# RainbowLED_2021_05_02_A.net
KiCad netlist of a schematic drawn in EAGLE
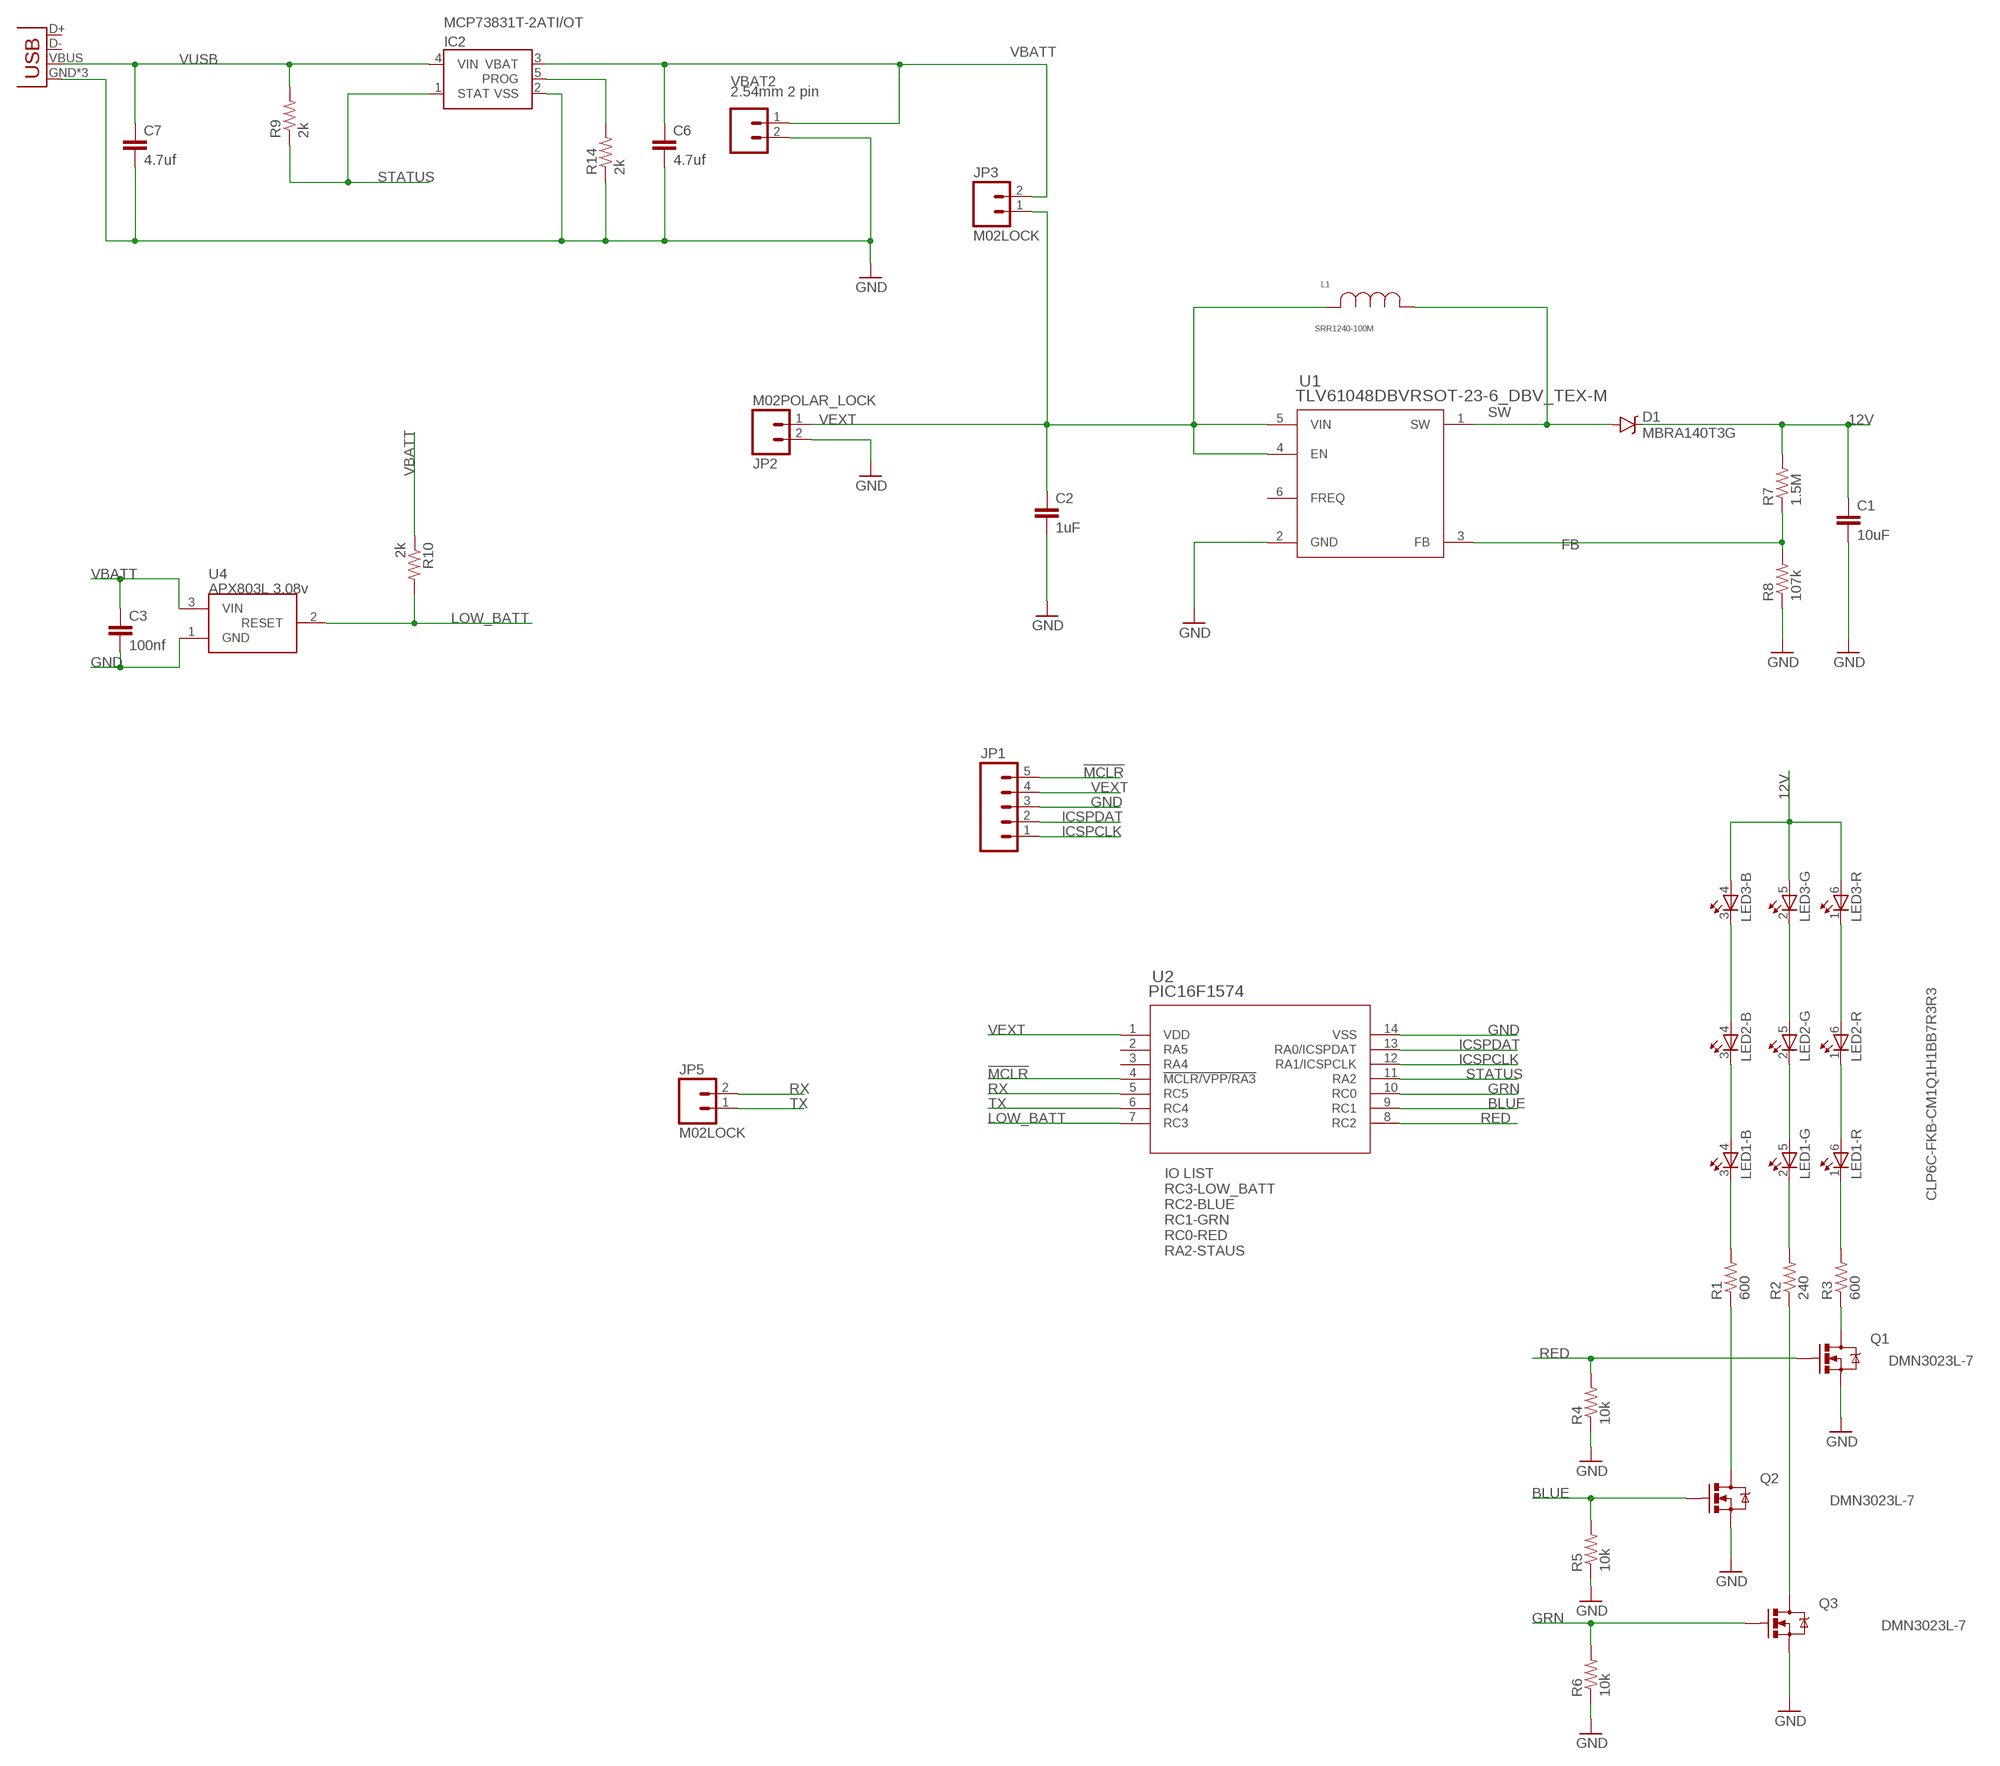
[diagram p0: schematic, sheet 1]

(export (version "E")
  (design (tool "Eeschema 10.0.6"))
  (components
    (comp (ref "C1")
      (value "10uF")
      (footprint "eagle-import:1206")
      (libsource (lib "eagle-import") (part "CAP1206"))
    )
    (comp (ref "C2")
      (value "1uF")
      (footprint "eagle-import:1206")
      (libsource (lib "eagle-import") (part "CAP1206"))
    )
    (comp (ref "C3")
      (value "100nf")
      (footprint "eagle-import:1206")
      (libsource (lib "eagle-import") (part "CAP1206"))
    )
    (comp (ref "C6")
      (value "4.7uf")
      (footprint "eagle-import:1206")
      (libsource (lib "eagle-import") (part "CAP1206"))
    )
    (comp (ref "C7")
      (value "4.7uf")
      (footprint "eagle-import:1206")
      (libsource (lib "eagle-import") (part "CAP1206"))
    )
    (comp (ref "D1")
      (value "MBRA140T3G")
      (footprint "eagle-import:SMA-DIODE")
      (libsource (lib "eagle-import") (part "DIODE-SCHOTTKY-MBRA140"))
    )
    (comp (ref "IC2")
      (value "MCP73831T-2ATI/OT")
      (footprint "eagle-import:SOT23-5")
      (libsource (lib "eagle-import") (part "MCP73831"))
    )
    (comp (ref "JP1")
      (value "M05LOCK")
      (footprint "eagle-import:1X05_LOCK")
      (libsource (lib "eagle-import") (part "M05LOCK"))
    )
    (comp (ref "JP2")
      (value "M02POLAR_LOCK")
      (footprint "eagle-import:MOLEX-1X2_LOCK")
      (libsource (lib "eagle-import") (part "M02POLAR_LOCK"))
    )
    (comp (ref "JP3")
      (value "M02LOCK")
      (footprint "eagle-import:1X02_LOCK")
      (libsource (lib "eagle-import") (part "M02LOCK"))
    )
    (comp (ref "JP4")
      (value "USB-MICROB")
      (footprint "eagle-import:USB-MICROB")
      (libsource (lib "eagle-import") (part "USB-MICROB"))
    )
    (comp (ref "JP5")
      (value "M02LOCK")
      (footprint "eagle-import:1X02_LOCK")
      (libsource (lib "eagle-import") (part "M02LOCK"))
    )
    (comp (ref "L1")
      (value "SRR1240-100M")
      (footprint "eagle-import:IND_BOURNS_SRR1240")
      (fields (field (name "MANUFACTURER_PART_NUMBER") "SRR1240100M"))
      (libsource (lib "eagle-import") (part "SRR1240-100M"))
    )
    (comp (ref "LED1")
      (value "CLX6F-FKC-CKNNQDGBB7A363")
      (footprint "eagle-import:PLCC-6")
      (libsource (lib "eagle-import") (part "OVSTRGBBCR8"))
    )
    (comp (ref "LED2")
      (value "CLX6F-FKC-CKNNQDGBB7A363")
      (footprint "eagle-import:PLCC-6")
      (libsource (lib "eagle-import") (part "OVSTRGBBCR8"))
    )
    (comp (ref "LED3")
      (value "CLX6F-FKC-CKNNQDGBB7A363")
      (footprint "eagle-import:PLCC-6")
      (libsource (lib "eagle-import") (part "OVSTRGBBCR8"))
    )
    (comp (ref "Q1")
      (value "DMN3023L-7")
      (footprint "eagle-import:SOT23-3")
      (libsource (lib "eagle-import") (part "MOSFET-NCHANNELBSS138"))
    )
    (comp (ref "Q2")
      (value "DMN3023L-7")
      (footprint "eagle-import:SOT23-3")
      (libsource (lib "eagle-import") (part "MOSFET-NCHANNELBSS138"))
    )
    (comp (ref "Q3")
      (value "DMN3023L-7")
      (footprint "eagle-import:SOT23-3")
      (libsource (lib "eagle-import") (part "MOSFET-NCHANNELBSS138"))
    )
    (comp (ref "R1")
      (value "600")
      (footprint "eagle-import:1206")
      (libsource (lib "eagle-import") (part "RESISTOR1206"))
    )
    (comp (ref "R2")
      (value "240")
      (footprint "eagle-import:1206")
      (libsource (lib "eagle-import") (part "RESISTOR1206"))
    )
    (comp (ref "R3")
      (value "600")
      (footprint "eagle-import:1206")
      (libsource (lib "eagle-import") (part "RESISTOR1206"))
    )
    (comp (ref "R4")
      (value "10k")
      (footprint "eagle-import:1206")
      (libsource (lib "eagle-import") (part "RESISTOR1206"))
    )
    (comp (ref "R5")
      (value "10k")
      (footprint "eagle-import:1206")
      (libsource (lib "eagle-import") (part "RESISTOR1206"))
    )
    (comp (ref "R6")
      (value "10k")
      (footprint "eagle-import:1206")
      (libsource (lib "eagle-import") (part "RESISTOR1206"))
    )
    (comp (ref "R7")
      (value "1.5M")
      (footprint "eagle-import:1206")
      (libsource (lib "eagle-import") (part "RESISTOR1206"))
    )
    (comp (ref "R8")
      (value "107k")
      (footprint "eagle-import:1206")
      (libsource (lib "eagle-import") (part "RESISTOR1206"))
    )
    (comp (ref "R9")
      (value "2k")
      (footprint "eagle-import:1206")
      (libsource (lib "eagle-import") (part "SparkFun-Resistors_RESISTOR1206"))
    )
    (comp (ref "R10")
      (value "2k")
      (footprint "eagle-import:1206")
      (libsource (lib "eagle-import") (part "SparkFun-Resistors_RESISTOR1206"))
    )
    (comp (ref "R14")
      (value "2k")
      (footprint "eagle-import:1206")
      (libsource (lib "eagle-import") (part "SparkFun-Resistors_RESISTOR1206"))
    )
    (comp (ref "U1")
      (value "TLV61048DBVRSOT-23-6_DBV_TEX-M")
      (footprint "eagle-import:SOT-23-6_DBV_TEX-M")
      (fields
        (field (name "MANUFACTURER_PART_NUMBER") "TLV61048DBVR")
        (field (name "COPYRIGHT") "Copyright (C) 2018 Accelerated Designs. All rights reserved")
      )
      (libsource (lib "eagle-import") (part "TLV61048DBVRSOT-23-6_DBV_TEX-M"))
    )
    (comp (ref "U2")
      (value "PIC16F1574")
      (footprint "eagle-import:SOIC14_SL")
      (fields (field (name "MANUFACTURER_PART_NUMBER") "PIC16F1503-I/SL"))
      (libsource (lib "eagle-import") (part "PIC16F1503-I/SL"))
    )
    (comp (ref "U4")
      (value "APX803L 3.08v")
      (footprint "eagle-import:SOT23")
      (libsource (lib "eagle-import") (part "ADP160"))
    )
    (comp (ref "VBAT2")
      (value "2.54mm 2 pin")
      (footprint "eagle-import:JST-2-PTH-VERT")
      (libsource (lib "eagle-import") (part "M02JST-PTH-VERT"))
    )
  )
  (nets
    (net (code "1") (name "/12V") (class "Default")
      (node (ref "C1") (pin "1") (pinfunction "1_1") (pintype "passive"))
      (node (ref "D1") (pin "C") (pinfunction "C_C") (pintype "passive"))
      (node (ref "LED3") (pin "4") (pinfunction "A_4") (pintype "passive"))
      (node (ref "LED3") (pin "5") (pinfunction "A_5") (pintype "passive"))
      (node (ref "LED3") (pin "6") (pinfunction "A_6") (pintype "passive"))
      (node (ref "R7") (pin "2") (pinfunction "2_2") (pintype "passive"))
    )
    (net (code "2") (name "/BLUE") (class "Default")
      (node (ref "Q2") (pin "1") (pinfunction "G_1") (pintype "passive"))
      (node (ref "R5") (pin "2") (pinfunction "2_2") (pintype "passive"))
      (node (ref "U2") (pin "9") (pinfunction "RC1_9") (pintype "bidirectional"))
    )
    (net (code "3") (name "/FB") (class "Default")
      (node (ref "R7") (pin "1") (pinfunction "1_1") (pintype "passive"))
      (node (ref "R8") (pin "2") (pinfunction "2_2") (pintype "passive"))
      (node (ref "U1") (pin "3") (pinfunction "FB_3") (pintype "input"))
    )
    (net (code "4") (name "/GRN") (class "Default")
      (node (ref "Q3") (pin "1") (pinfunction "G_1") (pintype "passive"))
      (node (ref "R6") (pin "2") (pinfunction "2_2") (pintype "passive"))
      (node (ref "U2") (pin "10") (pinfunction "RC0_10") (pintype "bidirectional"))
    )
    (net (code "5") (name "/ICSPCLK") (class "Default")
      (node (ref "JP1") (pin "1") (pinfunction "1_1") (pintype "passive"))
      (node (ref "U2") (pin "12") (pinfunction "RA1/ICSPCLK_12") (pintype "bidirectional"))
    )
    (net (code "6") (name "/ICSPDAT") (class "Default")
      (node (ref "JP1") (pin "2") (pinfunction "2_2") (pintype "passive"))
      (node (ref "U2") (pin "13") (pinfunction "RA0/ICSPDAT_13") (pintype "bidirectional"))
    )
    (net (code "7") (name "/LOW_BATT") (class "Default")
      (node (ref "R10") (pin "2") (pinfunction "2_2") (pintype "passive"))
      (node (ref "U2") (pin "7") (pinfunction "RC3_7") (pintype "bidirectional"))
      (node (ref "U4") (pin "2") (pinfunction "RESET_2") (pintype "bidirectional"))
    )
    (net (code "8") (name "/RED") (class "Default")
      (node (ref "Q1") (pin "1") (pinfunction "G_1") (pintype "passive"))
      (node (ref "R4") (pin "2") (pinfunction "2_2") (pintype "passive"))
      (node (ref "U2") (pin "8") (pinfunction "RC2_8") (pintype "bidirectional"))
    )
    (net (code "9") (name "/RX") (class "Default")
      (node (ref "JP5") (pin "2") (pinfunction "2_2") (pintype "passive"))
      (node (ref "U2") (pin "5") (pinfunction "RC5_5") (pintype "bidirectional"))
    )
    (net (code "10") (name "/STATUS") (class "Default")
      (node (ref "IC2") (pin "1") (pinfunction "STAT_1") (pintype "output"))
      (node (ref "R9") (pin "1") (pinfunction "1_1") (pintype "passive"))
      (node (ref "U2") (pin "11") (pinfunction "RA2_11") (pintype "bidirectional"))
    )
    (net (code "11") (name "/SW") (class "Default")
      (node (ref "D1") (pin "A") (pinfunction "A_A") (pintype "passive"))
      (node (ref "L1") (pin "1") (pinfunction "1_1") (pintype "passive"))
      (node (ref "U1") (pin "1") (pinfunction "SW_1") (pintype "power_in"))
    )
    (net (code "12") (name "/TX") (class "Default")
      (node (ref "JP5") (pin "1") (pinfunction "1_1") (pintype "passive"))
      (node (ref "U2") (pin "6") (pinfunction "RC4_6") (pintype "bidirectional"))
    )
    (net (code "13") (name "/VBATT") (class "Default")
      (node (ref "C3") (pin "1") (pinfunction "1_1") (pintype "passive"))
      (node (ref "C6") (pin "1") (pinfunction "1_1") (pintype "passive"))
      (node (ref "IC2") (pin "3") (pinfunction "VBAT_3") (pintype "power_in"))
      (node (ref "JP3") (pin "2") (pinfunction "2_2") (pintype "passive"))
      (node (ref "R10") (pin "1") (pinfunction "1_1") (pintype "passive"))
      (node (ref "U4") (pin "3") (pinfunction "VIN_3") (pintype "bidirectional"))
      (node (ref "VBAT2") (pin "1") (pinfunction "1_1") (pintype "passive"))
    )
    (net (code "14") (name "/VEXT") (class "Default")
      (node (ref "C2") (pin "1") (pinfunction "1_1") (pintype "passive"))
      (node (ref "JP1") (pin "4") (pinfunction "4_4") (pintype "passive"))
      (node (ref "JP2") (pin "1") (pinfunction "1_1") (pintype "passive"))
      (node (ref "JP3") (pin "1") (pinfunction "1_1") (pintype "passive"))
      (node (ref "L1") (pin "2") (pinfunction "2_2") (pintype "passive"))
      (node (ref "U1") (pin "4") (pinfunction "EN_4") (pintype "input"))
      (node (ref "U1") (pin "5") (pinfunction "VIN_5") (pintype "power_in"))
      (node (ref "U2") (pin "1") (pinfunction "VDD_1") (pintype "power_in"))
    )
    (net (code "15") (name "/VUSB") (class "Default")
      (node (ref "C7") (pin "1") (pinfunction "1_1") (pintype "passive"))
      (node (ref "IC2") (pin "4") (pinfunction "VIN_4") (pintype "power_in"))
      (node (ref "JP4") (pin "VBUS") (pinfunction "VBUS_VBUS") (pintype "bidirectional"))
      (node (ref "R9") (pin "2") (pinfunction "2_2") (pintype "passive"))
    )
    (net (code "16") (name "/~{MCLR}") (class "Default")
      (node (ref "JP1") (pin "5") (pinfunction "5_5") (pintype "passive"))
      (node (ref "U2") (pin "4") (pinfunction "~{MCLR/VPP/RA3}_4") (pintype "bidirectional"))
    )
    (net (code "17") (name "GND") (class "Default")
      (node (ref "C1") (pin "2") (pinfunction "2_2") (pintype "passive"))
      (node (ref "C2") (pin "2") (pinfunction "2_2") (pintype "passive"))
      (node (ref "C3") (pin "2") (pinfunction "2_2") (pintype "passive"))
      (node (ref "C6") (pin "2") (pinfunction "2_2") (pintype "passive"))
      (node (ref "C7") (pin "2") (pinfunction "2_2") (pintype "passive"))
      (node (ref "IC2") (pin "2") (pinfunction "VSS_2") (pintype "power_in"))
      (node (ref "JP1") (pin "3") (pinfunction "3_3") (pintype "passive"))
      (node (ref "JP2") (pin "2") (pinfunction "2_2") (pintype "passive"))
      (node (ref "JP4") (pin "GND") (pinfunction "GND_GND") (pintype "bidirectional"))
      (node (ref "JP4") (pin "MT1") (pinfunction "GND_MT1") (pintype "bidirectional"))
      (node (ref "JP4") (pin "MT2") (pinfunction "GND_MT2") (pintype "bidirectional"))
      (node (ref "Q1") (pin "2") (pinfunction "S_2") (pintype "passive"))
      (node (ref "Q2") (pin "2") (pinfunction "S_2") (pintype "passive"))
      (node (ref "Q3") (pin "2") (pinfunction "S_2") (pintype "passive"))
      (node (ref "R14") (pin "1") (pinfunction "1_1") (pintype "passive"))
      (node (ref "R4") (pin "1") (pinfunction "1_1") (pintype "passive"))
      (node (ref "R5") (pin "1") (pinfunction "1_1") (pintype "passive"))
      (node (ref "R6") (pin "1") (pinfunction "1_1") (pintype "passive"))
      (node (ref "R8") (pin "1") (pinfunction "1_1") (pintype "passive"))
      (node (ref "U1") (pin "2") (pinfunction "GND_2") (pintype "passive"))
      (node (ref "U2") (pin "14") (pinfunction "VSS_14") (pintype "power_in"))
      (node (ref "U4") (pin "1") (pinfunction "GND_1") (pintype "bidirectional"))
      (node (ref "VBAT2") (pin "2") (pinfunction "2_2") (pintype "passive"))
    )
    (net (code "18") (name "Net-(IC2-PROG)") (class "Default")
      (node (ref "IC2") (pin "5") (pinfunction "PROG_5") (pintype "input"))
      (node (ref "R14") (pin "2") (pinfunction "2_2") (pintype "passive"))
    )
    (net (code "19") (name "Net-(LED1A-A)") (class "Default")
      (node (ref "LED1") (pin "4") (pinfunction "A_4") (pintype "passive"))
      (node (ref "LED2") (pin "3") (pinfunction "C_3") (pintype "passive"))
    )
    (net (code "20") (name "Net-(LED1A-C)") (class "Default")
      (node (ref "LED1") (pin "3") (pinfunction "C_3") (pintype "passive"))
      (node (ref "R1") (pin "2") (pinfunction "2_2") (pintype "passive"))
    )
    (net (code "21") (name "Net-(LED1B-A)") (class "Default")
      (node (ref "LED1") (pin "5") (pinfunction "A_5") (pintype "passive"))
      (node (ref "LED2") (pin "2") (pinfunction "C_2") (pintype "passive"))
    )
    (net (code "22") (name "Net-(LED1B-C)") (class "Default")
      (node (ref "LED1") (pin "2") (pinfunction "C_2") (pintype "passive"))
      (node (ref "R2") (pin "2") (pinfunction "2_2") (pintype "passive"))
    )
    (net (code "23") (name "Net-(LED1C-A)") (class "Default")
      (node (ref "LED1") (pin "6") (pinfunction "A_6") (pintype "passive"))
      (node (ref "LED2") (pin "1") (pinfunction "C_1") (pintype "passive"))
    )
    (net (code "24") (name "Net-(LED1C-C)") (class "Default")
      (node (ref "LED1") (pin "1") (pinfunction "C_1") (pintype "passive"))
      (node (ref "R3") (pin "2") (pinfunction "2_2") (pintype "passive"))
    )
    (net (code "25") (name "Net-(LED2A-A)") (class "Default")
      (node (ref "LED2") (pin "4") (pinfunction "A_4") (pintype "passive"))
      (node (ref "LED3") (pin "3") (pinfunction "C_3") (pintype "passive"))
    )
    (net (code "26") (name "Net-(LED2B-A)") (class "Default")
      (node (ref "LED2") (pin "5") (pinfunction "A_5") (pintype "passive"))
      (node (ref "LED3") (pin "2") (pinfunction "C_2") (pintype "passive"))
    )
    (net (code "27") (name "Net-(LED2C-A)") (class "Default")
      (node (ref "LED2") (pin "6") (pinfunction "A_6") (pintype "passive"))
      (node (ref "LED3") (pin "1") (pinfunction "C_1") (pintype "passive"))
    )
    (net (code "28") (name "Net-(Q1-D)") (class "Default")
      (node (ref "Q1") (pin "3") (pinfunction "D_3") (pintype "passive"))
      (node (ref "R3") (pin "1") (pinfunction "1_1") (pintype "passive"))
    )
    (net (code "29") (name "Net-(Q2-D)") (class "Default")
      (node (ref "Q2") (pin "3") (pinfunction "D_3") (pintype "passive"))
      (node (ref "R1") (pin "1") (pinfunction "1_1") (pintype "passive"))
    )
    (net (code "30") (name "Net-(Q3-D)") (class "Default")
      (node (ref "Q3") (pin "3") (pinfunction "D_3") (pintype "passive"))
      (node (ref "R2") (pin "1") (pinfunction "1_1") (pintype "passive"))
    )
    (net (code "31") (name "unconnected-(JP4-PadD+)") (class "Default")
      (node (ref "JP4") (pin "D+") (pinfunction "D+_D+") (pintype "bidirectional"))
    )
    (net (code "32") (name "unconnected-(JP4-PadD-)") (class "Default")
      (node (ref "JP4") (pin "D-") (pinfunction "D-_D-") (pintype "bidirectional"))
    )
    (net (code "33") (name "unconnected-(U1-FREQ-Pad6)") (class "Default")
      (node (ref "U1") (pin "6") (pinfunction "FREQ_6") (pintype "input"))
    )
    (net (code "34") (name "unconnected-(U2-RA4-Pad3)") (class "Default")
      (node (ref "U2") (pin "3") (pinfunction "RA4_3") (pintype "bidirectional"))
    )
    (net (code "35") (name "unconnected-(U2-RA5-Pad2)") (class "Default")
      (node (ref "U2") (pin "2") (pinfunction "RA5_2") (pintype "bidirectional"))
    )
  )
)
